# Supply.net
KiCad netlist of a schematic drawn in EAGLE
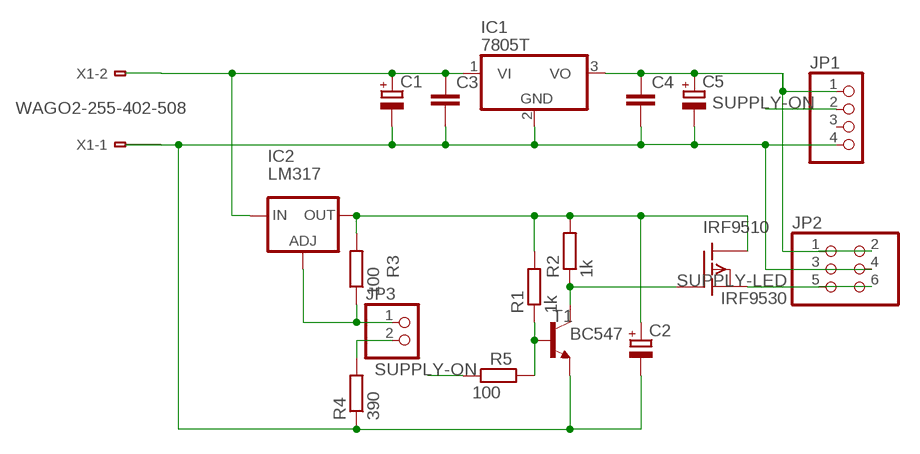
[diagram p0: schematic, sheet 1]

(export (version "E")
  (design (tool "Eeschema 10.0.6"))
  (components
    (comp (ref "C1")
      (value "CPOL-EUE5-10.5")
      (footprint "eagle-import:E5-10,5")
      (libsource (lib "eagle-import") (part "CPOL-EUE5-10.5"))
    )
    (comp (ref "C2")
      (value "CPOL-EUE5-10.5")
      (footprint "eagle-import:E5-10,5")
      (libsource (lib "eagle-import") (part "CPOL-EUE5-10.5"))
    )
    (comp (ref "C3")
      (value "C-EU050-024X044")
      (footprint "eagle-import:C050-024X044")
      (libsource (lib "eagle-import") (part "C-EU050-024X044"))
    )
    (comp (ref "C4")
      (value "C-EU050-024X044")
      (footprint "eagle-import:C050-024X044")
      (libsource (lib "eagle-import") (part "C-EU050-024X044"))
    )
    (comp (ref "C5")
      (value "CPOL-EUE2,5-6E")
      (footprint "eagle-import:E2,5-6E")
      (libsource (lib "eagle-import") (part "CPOL-EUE2,5-6E"))
    )
    (comp (ref "IC1")
      (value "7805T")
      (footprint "eagle-import:TO220H")
      (libsource (lib "eagle-import") (part "78T05"))
    )
    (comp (ref "IC2")
      (value "LM317")
      (footprint "eagle-import:317TL")
      (libsource (lib "eagle-import") (part "LM317TL"))
    )
    (comp (ref "IRF9510")
      (value "IRF9530")
      (footprint "eagle-import:TO220")
      (libsource (lib "eagle-import") (part "IRF9530"))
    )
    (comp (ref "JP1")
      (value "PINHD-1X4")
      (footprint "eagle-import:1X04")
      (libsource (lib "eagle-import") (part "PINHD-1X4"))
    )
    (comp (ref "JP2")
      (value "PINHD-2X3")
      (footprint "eagle-import:2X03")
      (libsource (lib "eagle-import") (part "PINHD-2X3"))
    )
    (comp (ref "JP3")
      (value "PINHD-1X2")
      (footprint "eagle-import:1X02")
      (libsource (lib "eagle-import") (part "PINHD-1X2"))
    )
    (comp (ref "R1")
      (value "1k")
      (footprint "eagle-import:0207_7")
      (libsource (lib "eagle-import") (part "R-EU_0207/7"))
    )
    (comp (ref "R2")
      (value "1k")
      (footprint "eagle-import:0207_7")
      (libsource (lib "eagle-import") (part "R-EU_0207/7"))
    )
    (comp (ref "R3")
      (value "100")
      (footprint "eagle-import:0207_7")
      (libsource (lib "eagle-import") (part "R-EU_0207/7"))
    )
    (comp (ref "R4")
      (value "390")
      (footprint "eagle-import:0207_7")
      (libsource (lib "eagle-import") (part "R-EU_0207/7"))
    )
    (comp (ref "R5")
      (value "100")
      (footprint "eagle-import:0207_7")
      (libsource (lib "eagle-import") (part "R-EU_0207/7"))
    )
    (comp (ref "T1")
      (value "BC547")
      (footprint "eagle-import:TO92-CBE")
      (libsource (lib "eagle-import") (part "-NPN-TO92-CBEBC547"))
    )
    (comp (ref "X1")
      (value "WAGO2-255-402-508")
      (footprint "eagle-import:255-402-508")
      (libsource (lib "eagle-import") (part "WAGO2-255-402-508"))
    )
  )
  (nets
    (net (code "1") (name "/SUPPLY-LED") (class "Default")
      (node (ref "IRF9510") (pin "3") (pinfunction "S_3") (pintype "passive"))
      (node (ref "JP2") (pin "5") (pinfunction "5_5") (pintype "passive"))
      (node (ref "JP2") (pin "6") (pinfunction "6_6") (pintype "passive"))
    )
    (net (code "2") (name "/SUPPLY-ON") (class "Default")
      (node (ref "JP1") (pin "2") (pinfunction "2_2") (pintype "passive"))
      (node (ref "R5") (pin "1") (pinfunction "1_1") (pintype "passive"))
    )
    (net (code "3") (name "Net-(IC1-GND)") (class "Default")
      (node (ref "C1") (pin "-") (pinfunction "-_-") (pintype "passive"))
      (node (ref "C2") (pin "-") (pinfunction "-_-") (pintype "passive"))
      (node (ref "C3") (pin "2") (pinfunction "2_2") (pintype "passive"))
      (node (ref "C4") (pin "2") (pinfunction "2_2") (pintype "passive"))
      (node (ref "C5") (pin "-") (pinfunction "-_-") (pintype "passive"))
      (node (ref "IC1") (pin "2") (pinfunction "GND_2") (pintype "passive"))
      (node (ref "JP1") (pin "4") (pinfunction "4_4") (pintype "passive"))
      (node (ref "JP2") (pin "3") (pinfunction "3_3") (pintype "passive"))
      (node (ref "JP2") (pin "4") (pinfunction "4_4") (pintype "passive"))
      (node (ref "R4") (pin "1") (pinfunction "1_1") (pintype "passive"))
      (node (ref "T1") (pin "E") (pinfunction "E_E") (pintype "passive"))
      (node (ref "X1") (pin "B1") (pinfunction "B1_B1") (pintype "passive"))
    )
    (net (code "4") (name "Net-(IC1-VI)") (class "Default")
      (node (ref "C1") (pin "+") (pinfunction "+_+") (pintype "passive"))
      (node (ref "C3") (pin "1") (pinfunction "1_1") (pintype "passive"))
      (node (ref "IC1") (pin "1") (pinfunction "VI_1") (pintype "input"))
      (node (ref "IC2") (pin "3") (pinfunction "IN_3") (pintype "input"))
      (node (ref "X1") (pin "B2") (pinfunction "B1_B2") (pintype "passive"))
    )
    (net (code "5") (name "Net-(IC1-VO)") (class "Default")
      (node (ref "C4") (pin "1") (pinfunction "1_1") (pintype "passive"))
      (node (ref "C5") (pin "+") (pinfunction "+_+") (pintype "passive"))
      (node (ref "IC1") (pin "3") (pinfunction "VO_3") (pintype "passive"))
      (node (ref "JP1") (pin "1") (pinfunction "1_1") (pintype "passive"))
      (node (ref "JP2") (pin "1") (pinfunction "1_1") (pintype "passive"))
      (node (ref "JP2") (pin "2") (pinfunction "2_2") (pintype "passive"))
    )
    (net (code "6") (name "Net-(IC2-ADJ)") (class "Default")
      (node (ref "IC2") (pin "1") (pinfunction "ADJ_1") (pintype "input"))
      (node (ref "JP3") (pin "1") (pinfunction "1_1") (pintype "passive"))
      (node (ref "R3") (pin "1") (pinfunction "1_1") (pintype "passive"))
    )
    (net (code "7") (name "Net-(IC2-OUT)") (class "Default")
      (node (ref "C2") (pin "+") (pinfunction "+_+") (pintype "passive"))
      (node (ref "IC2") (pin "2") (pinfunction "OUT_2") (pintype "passive"))
      (node (ref "IRF9510") (pin "2") (pinfunction "D_2") (pintype "passive"))
      (node (ref "R1") (pin "2") (pinfunction "2_2") (pintype "passive"))
      (node (ref "R2") (pin "2") (pinfunction "2_2") (pintype "passive"))
      (node (ref "R3") (pin "2") (pinfunction "2_2") (pintype "passive"))
    )
    (net (code "8") (name "Net-(IRF9510-G)") (class "Default")
      (node (ref "IRF9510") (pin "1") (pinfunction "G_1") (pintype "passive"))
      (node (ref "R2") (pin "1") (pinfunction "1_1") (pintype "passive"))
      (node (ref "T1") (pin "C") (pinfunction "C_C") (pintype "passive"))
    )
    (net (code "9") (name "Net-(JP3-Pad2)") (class "Default")
      (node (ref "JP3") (pin "2") (pinfunction "2_2") (pintype "passive"))
      (node (ref "R4") (pin "2") (pinfunction "2_2") (pintype "passive"))
    )
    (net (code "10") (name "Net-(R1-Pad1)") (class "Default")
      (node (ref "R1") (pin "1") (pinfunction "1_1") (pintype "passive"))
      (node (ref "R5") (pin "2") (pinfunction "2_2") (pintype "passive"))
      (node (ref "T1") (pin "B") (pinfunction "B_B") (pintype "passive"))
    )
    (net (code "11") (name "unconnected-(JP1-Pad3)") (class "Default")
      (node (ref "JP1") (pin "3") (pinfunction "3_3") (pintype "passive"))
    )
    (net (code "12") (name "unconnected-(X1-PadA1)") (class "Default")
      (node (ref "X1") (pin "A1") (pinfunction "A1_A1") (pintype "passive"))
    )
    (net (code "13") (name "unconnected-(X1B-A1-PadA2)") (class "Default")
      (node (ref "X1") (pin "A2") (pinfunction "A1_A2") (pintype "passive"))
    )
  )
)
